# PCM5102A.net
KiCad netlist of a schematic drawn in Altium Designer
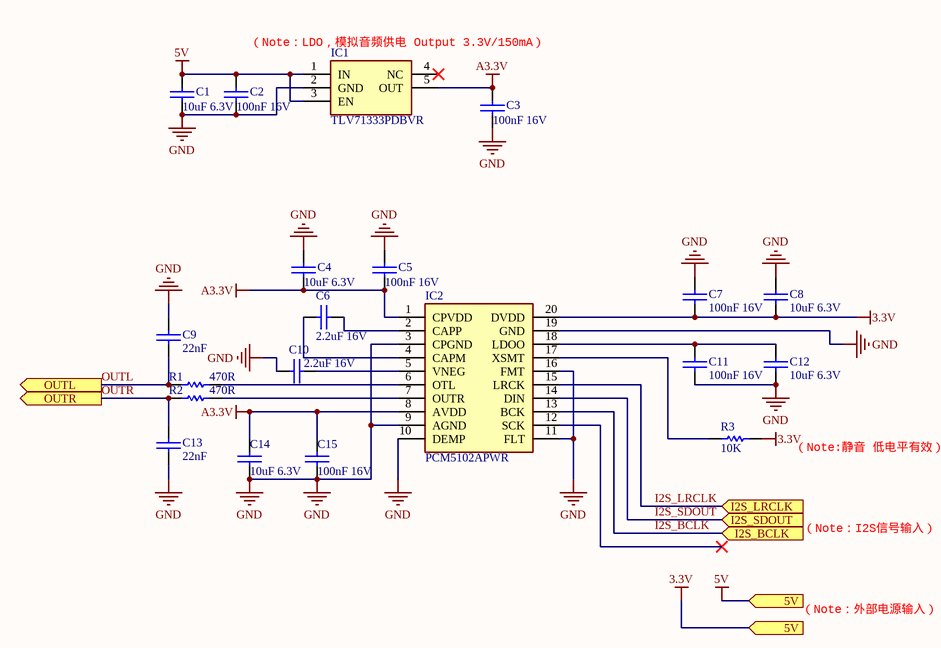
[diagram p0: PCM5102A .SchDoc]

(export (version "E")
  (design (tool "Eeschema 10.0.6"))
  (components
    (comp (ref "C1") (value "10uF 6.3V") (footprint "0603C") (libsource (lib "Capacitance") (part "CAP-NP")))
    (comp (ref "C2") (value "100nF 16V") (footprint "0402C") (libsource (lib "Capacitance") (part "CAP-NP")))
    (comp (ref "C3") (value "100nF 16V") (footprint "0402C") (libsource (lib "Capacitance") (part "CAP-NP")))
    (comp (ref "C4") (value "10uF 6.3V") (footprint "0603C") (libsource (lib "Capacitance") (part "CAP-NP")))
    (comp (ref "C5") (value "100nF 16V") (footprint "0402C") (libsource (lib "Capacitance") (part "CAP-NP")))
    (comp (ref "C6") (value "2.2uF 16V") (footprint "0402C") (libsource (lib "Capacitance") (part "CAP-NP")))
    (comp (ref "C7") (value "100nF 16V") (footprint "0402C") (libsource (lib "Capacitance") (part "CAP-NP")))
    (comp (ref "C8") (value "10uF 6.3V") (footprint "0603C") (libsource (lib "Capacitance") (part "CAP-NP")))
    (comp (ref "C9") (value "22nF") (footprint "0402C") (libsource (lib "Capacitance") (part "CAP-NP")))
    (comp (ref "C10") (value "2.2uF 16V") (footprint "0402C") (libsource (lib "Capacitance") (part "CAP-NP")))
    (comp (ref "C11") (value "100nF 16V") (footprint "0402C") (libsource (lib "Capacitance") (part "CAP-NP")))
    (comp (ref "C12") (value "10uF 6.3V") (footprint "0603C") (libsource (lib "Capacitance") (part "CAP-NP")))
    (comp (ref "C13") (value "22nF") (footprint "0402C") (libsource (lib "Capacitance") (part "CAP-NP")))
    (comp (ref "C14") (value "10uF 6.3V") (footprint "0603C") (libsource (lib "Capacitance") (part "CAP-NP")))
    (comp (ref "C15") (value "100nF 16V") (footprint "0402C") (libsource (lib "Capacitance") (part "CAP-NP")))
    (comp (ref "IC1")
      (value "TLV71333PDBVR")
      (footprint "SamacSys:SOT95P280X145-5N")
      (description "Integrated Circuit")
      (fields (field (name "MOUSER PART NUMBER") "595-TLV71333PDBVR"))
      (libsource (lib "*") (part "TLV71333PDBVR"))
    )
    (comp (ref "IC2")
      (value "PCM5102APWR")
      (footprint "SamacSys:SOP65P640X120-20N")
      (description "Integrated Circuit")
      (fields (field (name "MOUSER PART NUMBER") "595-PCM5102APWR"))
      (libsource (lib "*") (part "PCM5102APWR"))
    )
    (comp (ref "R1") (value "470R") (footprint "0402R") (libsource (lib "Resistors") (part "RES")))
    (comp (ref "R2") (value "470R") (footprint "0402R") (libsource (lib "Resistors") (part "RES")))
    (comp (ref "R3") (value "10K") (footprint "0402R") (libsource (lib "Resistors") (part "RES")))
  )
  (nets
    (net (code "1") (name "/I2S_BCLK") (class "Default")
      (node (ref "IC2") (pin "13") (pinfunction "BCK_13") (pintype "passive"))
    )
    (net (code "2") (name "/I2S_LRCLK") (class "Default")
      (node (ref "IC2") (pin "15") (pinfunction "LRCK_15") (pintype "passive"))
    )
    (net (code "3") (name "/I2S_SDOUT") (class "Default")
      (node (ref "IC2") (pin "14") (pinfunction "DIN_14") (pintype "passive"))
    )
    (net (code "4") (name "/OUTL") (class "Default")
      (node (ref "C9") (pin "1") (pinfunction "1_1") (pintype "passive"))
      (node (ref "R1") (pin "2") (pinfunction "2_2") (pintype "passive"))
    )
    (net (code "5") (name "/OUTR") (class "Default")
      (node (ref "C13") (pin "2") (pinfunction "2_2") (pintype "passive"))
      (node (ref "R2") (pin "2") (pinfunction "2_2") (pintype "passive"))
    )
    (net (code "6") (name "3.3V") (class "Default")
      (node (ref "C1") (pin "2") (pinfunction "2_2") (pintype "passive"))
      (node (ref "C2") (pin "2") (pinfunction "2_2") (pintype "passive"))
      (node (ref "C7") (pin "1") (pinfunction "1_1") (pintype "passive"))
      (node (ref "C8") (pin "1") (pinfunction "1_1") (pintype "passive"))
      (node (ref "IC1") (pin "1") (pinfunction "IN_1") (pintype "passive"))
      (node (ref "IC1") (pin "3") (pinfunction "EN_3") (pintype "passive"))
      (node (ref "IC2") (pin "20") (pinfunction "DVDD_20") (pintype "passive"))
      (node (ref "R3") (pin "1") (pinfunction "1_1") (pintype "passive"))
    )
    (net (code "7") (name "A3.3V") (class "Default")
      (node (ref "C14") (pin "2") (pinfunction "2_2") (pintype "passive"))
      (node (ref "C15") (pin "2") (pinfunction "2_2") (pintype "passive"))
      (node (ref "C3") (pin "2") (pinfunction "2_2") (pintype "passive"))
      (node (ref "C4") (pin "1") (pinfunction "1_1") (pintype "passive"))
      (node (ref "C5") (pin "1") (pinfunction "1_1") (pintype "passive"))
      (node (ref "IC1") (pin "5") (pinfunction "OUT_5") (pintype "passive"))
      (node (ref "IC2") (pin "1") (pinfunction "CPVDD_1") (pintype "passive"))
      (node (ref "IC2") (pin "8") (pinfunction "AVDD_8") (pintype "passive"))
    )
    (net (code "8") (name "GND") (class "Default")
      (node (ref "C1") (pin "1") (pinfunction "1_1") (pintype "passive"))
      (node (ref "C10") (pin "2") (pinfunction "2_2") (pintype "passive"))
      (node (ref "C11") (pin "1") (pinfunction "1_1") (pintype "passive"))
      (node (ref "C12") (pin "1") (pinfunction "1_1") (pintype "passive"))
      (node (ref "C13") (pin "1") (pinfunction "1_1") (pintype "passive"))
      (node (ref "C14") (pin "1") (pinfunction "1_1") (pintype "passive"))
      (node (ref "C15") (pin "1") (pinfunction "1_1") (pintype "passive"))
      (node (ref "C2") (pin "1") (pinfunction "1_1") (pintype "passive"))
      (node (ref "C3") (pin "1") (pinfunction "1_1") (pintype "passive"))
      (node (ref "C4") (pin "2") (pinfunction "2_2") (pintype "passive"))
      (node (ref "C5") (pin "2") (pinfunction "2_2") (pintype "passive"))
      (node (ref "C7") (pin "2") (pinfunction "2_2") (pintype "passive"))
      (node (ref "C8") (pin "2") (pinfunction "2_2") (pintype "passive"))
      (node (ref "C9") (pin "2") (pinfunction "2_2") (pintype "passive"))
      (node (ref "IC1") (pin "2") (pinfunction "GND_2") (pintype "passive"))
      (node (ref "IC2") (pin "10") (pinfunction "DEMP_10") (pintype "passive"))
      (node (ref "IC2") (pin "11") (pinfunction "FLT_11") (pintype "passive"))
      (node (ref "IC2") (pin "16") (pinfunction "FMT_16") (pintype "passive"))
      (node (ref "IC2") (pin "19") (pinfunction "GND_19") (pintype "passive"))
      (node (ref "IC2") (pin "3") (pinfunction "CPGND_3") (pintype "passive"))
      (node (ref "IC2") (pin "9") (pinfunction "AGND_9") (pintype "passive"))
    )
    (net (code "9") (name "Net-(IC2-CAPM)") (class "Default")
      (node (ref "C6") (pin "2") (pinfunction "2_2") (pintype "passive"))
      (node (ref "IC2") (pin "4") (pinfunction "CAPM_4") (pintype "passive"))
    )
    (net (code "10") (name "Net-(IC2-CAPP)") (class "Default")
      (node (ref "C6") (pin "1") (pinfunction "1_1") (pintype "passive"))
      (node (ref "IC2") (pin "2") (pinfunction "CAPP_2") (pintype "passive"))
    )
    (net (code "11") (name "Net-(IC2-LDOO)") (class "Default")
      (node (ref "C11") (pin "2") (pinfunction "2_2") (pintype "passive"))
      (node (ref "C12") (pin "2") (pinfunction "2_2") (pintype "passive"))
      (node (ref "IC2") (pin "18") (pinfunction "LDOO_18") (pintype "passive"))
    )
    (net (code "12") (name "Net-(IC2-OTL)") (class "Default")
      (node (ref "IC2") (pin "6") (pinfunction "OTL_6") (pintype "passive"))
      (node (ref "R1") (pin "1") (pinfunction "1_1") (pintype "passive"))
    )
    (net (code "13") (name "Net-(IC2-OUTR)") (class "Default")
      (node (ref "IC2") (pin "7") (pinfunction "OUTR_7") (pintype "passive"))
      (node (ref "R2") (pin "1") (pinfunction "1_1") (pintype "passive"))
    )
    (net (code "14") (name "Net-(IC2-VNEG)") (class "Default")
      (node (ref "C10") (pin "1") (pinfunction "1_1") (pintype "passive"))
      (node (ref "IC2") (pin "5") (pinfunction "VNEG_5") (pintype "passive"))
    )
    (net (code "15") (name "Net-(IC2-XSMT)") (class "Default")
      (node (ref "IC2") (pin "17") (pinfunction "XSMT_17") (pintype "passive"))
      (node (ref "R3") (pin "2") (pinfunction "2_2") (pintype "passive"))
    )
    (net (code "16") (name "unconnected-(IC1-NC-Pad4)") (class "Default")
      (node (ref "IC1") (pin "4") (pinfunction "NC_4") (pintype "passive+no_connect"))
    )
    (net (code "17") (name "unconnected-(IC2-SCK-Pad12)") (class "Default")
      (node (ref "IC2") (pin "12") (pinfunction "SCK_12") (pintype "passive+no_connect"))
    )
  )
)
